# ECG_AFE_ADS1292.net
KiCad netlist of a schematic drawn in Altium Designer
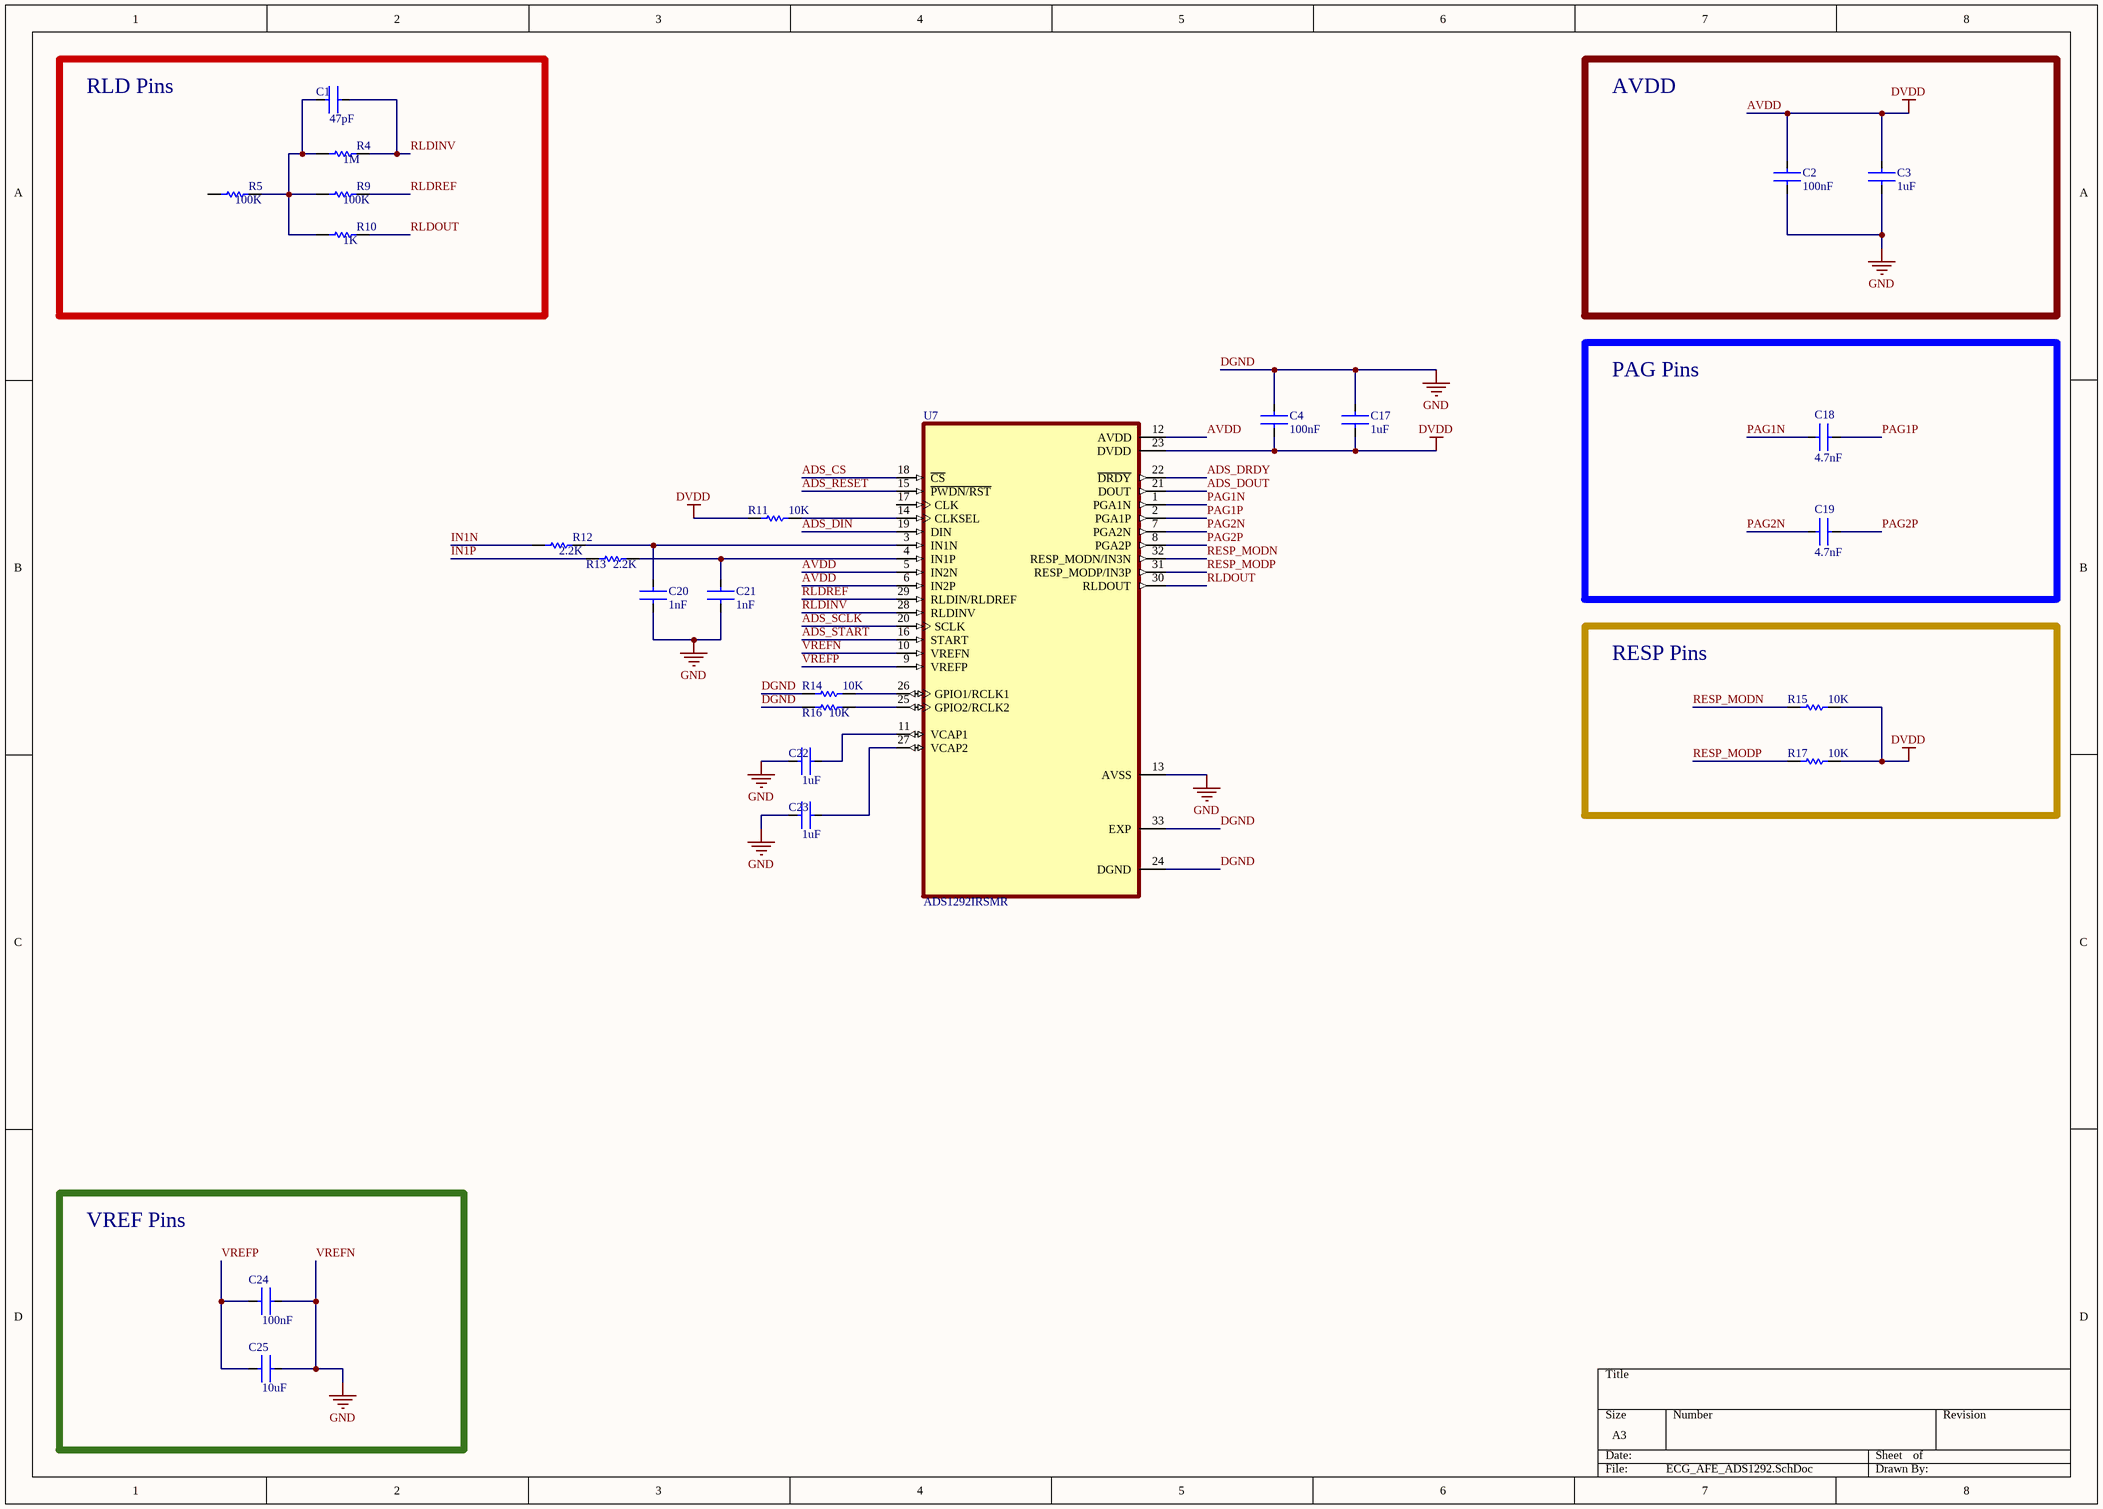
[diagram p0: ECG_AFE_ADS1292.SchDoc]

(export (version "E")
  (design (tool "Eeschema 10.0.6"))
  (components
    (comp (ref "C1")
      (value "47pF")
      (footprint "C_0805")
      (libsource (lib "ecg_device_components") (part "CAP-0805-16V-SMD-IPC_A"))
    )
    (comp (ref "C2")
      (value "100nF")
      (footprint "C_0805")
      (libsource (lib "ecg_device_components") (part "CAP-0805-16V-SMD-IPC_A"))
    )
    (comp (ref "C3")
      (value "1uF")
      (footprint "C_0805")
      (libsource (lib "ecg_device_components") (part "CAP-0805-16V-SMD-IPC_A"))
    )
    (comp (ref "C4")
      (value "100nF")
      (footprint "C_0805")
      (libsource (lib "ecg_device_components") (part "CAP-0805-16V-SMD-IPC_A"))
    )
    (comp (ref "C17")
      (value "1uF")
      (footprint "C_0805")
      (libsource (lib "ecg_device_components") (part "CAP-0805-16V-SMD-IPC_A"))
    )
    (comp (ref "C18")
      (value "4.7nF")
      (footprint "C_0805")
      (libsource (lib "ecg_device_components") (part "CAP-0805-16V-SMD-IPC_A"))
    )
    (comp (ref "C19")
      (value "4.7nF")
      (footprint "C_0805")
      (libsource (lib "ecg_device_components") (part "CAP-0805-16V-SMD-IPC_A"))
    )
    (comp (ref "C20")
      (value "1nF")
      (footprint "C_0805")
      (libsource (lib "ecg_device_components") (part "CAP-0805-16V-SMD-IPC_A"))
    )
    (comp (ref "C21")
      (value "1nF")
      (footprint "C_0805")
      (libsource (lib "ecg_device_components") (part "CAP-0805-16V-SMD-IPC_A"))
    )
    (comp (ref "C22")
      (value "1uF")
      (footprint "C_0805")
      (libsource (lib "ecg_device_components") (part "CAP-0805-16V-SMD-IPC_A"))
    )
    (comp (ref "C23")
      (value "1uF")
      (footprint "C_0805")
      (libsource (lib "ecg_device_components") (part "CAP-0805-16V-SMD-IPC_A"))
    )
    (comp (ref "C24")
      (value "100nF")
      (footprint "C_0805")
      (libsource (lib "ecg_device_components") (part "CAP-0805-16V-SMD-IPC_A"))
    )
    (comp (ref "C25")
      (value "10uF")
      (footprint "C_0805")
      (libsource (lib "ecg_device_components") (part "CAP-0805-16V-SMD-IPC_A"))
    )
    (comp (ref "R4")
      (value "1M")
      (footprint "RESC2013X60X35ML10T20")
      (libsource (lib "ecg_device_components") (part "10k 0805"))
    )
    (comp (ref "R5")
      (value "100K")
      (footprint "RESC2013X60X35ML10T20")
      (libsource (lib "ecg_device_components") (part "10k 0805"))
    )
    (comp (ref "R9")
      (value "100K")
      (footprint "RESC2013X60X35ML10T20")
      (libsource (lib "ecg_device_components") (part "10k 0805"))
    )
    (comp (ref "R10")
      (value "1K")
      (footprint "RESC2013X60X35ML10T20")
      (libsource (lib "ecg_device_components") (part "10k 0805"))
    )
    (comp (ref "R11")
      (value "10K")
      (footprint "RESC2013X60X35ML10T20")
      (libsource (lib "ecg_device_components") (part "10k 0805"))
    )
    (comp (ref "R12")
      (value "2.2K")
      (footprint "RESC2013X60X35ML10T20")
      (libsource (lib "ecg_device_components") (part "10k 0805"))
    )
    (comp (ref "R13")
      (value "2.2K")
      (footprint "RESC2013X60X35ML10T20")
      (libsource (lib "ecg_device_components") (part "10k 0805"))
    )
    (comp (ref "R14")
      (value "10K")
      (footprint "RESC2013X60X35ML10T20")
      (libsource (lib "ecg_device_components") (part "10k 0805"))
    )
    (comp (ref "R15")
      (value "10K")
      (footprint "RESC2013X60X35ML10T20")
      (libsource (lib "ecg_device_components") (part "10k 0805"))
    )
    (comp (ref "R16")
      (value "10K")
      (footprint "RESC2013X60X35ML10T20")
      (libsource (lib "ecg_device_components") (part "10k 0805"))
    )
    (comp (ref "R17")
      (value "10K")
      (footprint "RESC2013X60X35ML10T20")
      (libsource (lib "ecg_device_components") (part "10k 0805"))
    )
    (comp (ref "U7")
      (value "ADS1292IRSMR")
      (footprint "QFN40P400X400X100-33N")
      (description "24-bit, 2-ch, Low-Power Analog Front END (AFE) for ECG Applications")
      (fields (field (name "MF") "Texas Instruments"))
      (libsource (lib "ecg_device_components") (part "ADS1292IRSMR"))
    )
  )
  (nets
    (net (code "1") (name "/ADS_CS") (class "Default")
      (node (ref "U7") (pin "18") (pinfunction "~{CS}_18") (pintype "input"))
    )
    (net (code "2") (name "/ADS_DIN") (class "Default")
      (node (ref "U7") (pin "19") (pinfunction "DIN_19") (pintype "input"))
    )
    (net (code "3") (name "/ADS_DOUT") (class "Default")
      (node (ref "U7") (pin "21") (pinfunction "DOUT_21") (pintype "output"))
    )
    (net (code "4") (name "/ADS_DRDY") (class "Default")
      (node (ref "U7") (pin "22") (pinfunction "~{DRDY}_22") (pintype "output"))
    )
    (net (code "5") (name "/ADS_RESET") (class "Default")
      (node (ref "U7") (pin "15") (pinfunction "~{PWDN/RST}_15") (pintype "input"))
    )
    (net (code "6") (name "/ADS_SCLK") (class "Default")
      (node (ref "U7") (pin "20") (pinfunction "SCLK_20") (pintype "input"))
    )
    (net (code "7") (name "/ADS_START") (class "Default")
      (node (ref "U7") (pin "16") (pinfunction "START_16") (pintype "input"))
    )
    (net (code "8") (name "/IN1N") (class "Default")
      (node (ref "R12") (pin "1") (pinfunction "1_1") (pintype "passive"))
    )
    (net (code "9") (name "/IN1P") (class "Default")
      (node (ref "R13") (pin "1") (pinfunction "1_1") (pintype "passive"))
    )
    (net (code "10") (name "/PAG1N") (class "Default")
      (node (ref "C18") (pin "2") (pinfunction "2_2") (pintype "passive"))
      (node (ref "U7") (pin "1") (pinfunction "PGA1N_1") (pintype "output"))
    )
    (net (code "11") (name "/PAG1P") (class "Default")
      (node (ref "C18") (pin "1") (pinfunction "1_1") (pintype "passive"))
      (node (ref "U7") (pin "2") (pinfunction "PGA1P_2") (pintype "output"))
    )
    (net (code "12") (name "/PAG2N") (class "Default")
      (node (ref "C19") (pin "2") (pinfunction "2_2") (pintype "passive"))
      (node (ref "U7") (pin "7") (pinfunction "PGA2N_7") (pintype "output"))
    )
    (net (code "13") (name "/PAG2P") (class "Default")
      (node (ref "C19") (pin "1") (pinfunction "1_1") (pintype "passive"))
      (node (ref "U7") (pin "8") (pinfunction "PGA2P_8") (pintype "output"))
    )
    (net (code "14") (name "/RESP_MODN") (class "Default")
      (node (ref "R15") (pin "1") (pinfunction "1_1") (pintype "passive"))
      (node (ref "U7") (pin "32") (pinfunction "RESP_MODN/IN3N_32") (pintype "output"))
    )
    (net (code "15") (name "/RESP_MODP") (class "Default")
      (node (ref "R17") (pin "1") (pinfunction "1_1") (pintype "passive"))
      (node (ref "U7") (pin "31") (pinfunction "RESP_MODP/IN3P_31") (pintype "output"))
    )
    (net (code "16") (name "/RLDINV") (class "Default")
      (node (ref "C1") (pin "2") (pinfunction "2_2") (pintype "passive"))
      (node (ref "R4") (pin "2") (pinfunction "2_2") (pintype "passive"))
      (node (ref "U7") (pin "28") (pinfunction "RLDINV_28") (pintype "input"))
    )
    (net (code "17") (name "/RLDOUT") (class "Default")
      (node (ref "R10") (pin "2") (pinfunction "2_2") (pintype "passive"))
      (node (ref "U7") (pin "30") (pinfunction "RLDOUT_30") (pintype "output"))
    )
    (net (code "18") (name "/RLDREF") (class "Default")
      (node (ref "R9") (pin "2") (pinfunction "2_2") (pintype "passive"))
      (node (ref "U7") (pin "29") (pinfunction "RLDIN/RLDREF_29") (pintype "input"))
    )
    (net (code "19") (name "/VREFP") (class "Default")
      (node (ref "C24") (pin "1") (pinfunction "1_1") (pintype "passive"))
      (node (ref "C25") (pin "1") (pinfunction "1_1") (pintype "passive"))
      (node (ref "U7") (pin "9") (pinfunction "VREFP_9") (pintype "input"))
    )
    (net (code "20") (name "DVDD") (class "Default")
      (node (ref "C17") (pin "1") (pinfunction "1_1") (pintype "passive"))
      (node (ref "C2") (pin "2") (pinfunction "2_2") (pintype "passive"))
      (node (ref "C3") (pin "2") (pinfunction "2_2") (pintype "passive"))
      (node (ref "C4") (pin "1") (pinfunction "1_1") (pintype "passive"))
      (node (ref "R11") (pin "1") (pinfunction "1_1") (pintype "passive"))
      (node (ref "R15") (pin "2") (pinfunction "2_2") (pintype "passive"))
      (node (ref "R17") (pin "2") (pinfunction "2_2") (pintype "passive"))
      (node (ref "U7") (pin "12") (pinfunction "AVDD_12") (pintype "power_in"))
      (node (ref "U7") (pin "23") (pinfunction "DVDD_23") (pintype "power_in"))
      (node (ref "U7") (pin "5") (pinfunction "IN2N_5") (pintype "input"))
      (node (ref "U7") (pin "6") (pinfunction "IN2P_6") (pintype "input"))
    )
    (net (code "21") (name "GND") (class "Default")
      (node (ref "C17") (pin "2") (pinfunction "2_2") (pintype "passive"))
      (node (ref "C2") (pin "1") (pinfunction "1_1") (pintype "passive"))
      (node (ref "C20") (pin "1") (pinfunction "1_1") (pintype "passive"))
      (node (ref "C21") (pin "1") (pinfunction "1_1") (pintype "passive"))
      (node (ref "C22") (pin "1") (pinfunction "1_1") (pintype "passive"))
      (node (ref "C23") (pin "1") (pinfunction "1_1") (pintype "passive"))
      (node (ref "C24") (pin "2") (pinfunction "2_2") (pintype "passive"))
      (node (ref "C25") (pin "2") (pinfunction "2_2") (pintype "passive"))
      (node (ref "C3") (pin "1") (pinfunction "1_1") (pintype "passive"))
      (node (ref "C4") (pin "2") (pinfunction "2_2") (pintype "passive"))
      (node (ref "R14") (pin "1") (pinfunction "1_1") (pintype "passive"))
      (node (ref "R16") (pin "1") (pinfunction "1_1") (pintype "passive"))
      (node (ref "U7") (pin "10") (pinfunction "VREFN_10") (pintype "input"))
      (node (ref "U7") (pin "13") (pinfunction "AVSS_13") (pintype "power_in"))
      (node (ref "U7") (pin "24") (pinfunction "DGND_24") (pintype "power_in"))
      (node (ref "U7") (pin "33") (pinfunction "EXP_33") (pintype "power_in"))
    )
    (net (code "22") (name "Net-(C1-Pad1)") (class "Default")
      (node (ref "C1") (pin "1") (pinfunction "1_1") (pintype "passive"))
      (node (ref "R10") (pin "1") (pinfunction "1_1") (pintype "passive"))
      (node (ref "R4") (pin "1") (pinfunction "1_1") (pintype "passive"))
      (node (ref "R5") (pin "2") (pinfunction "2_2") (pintype "passive"))
      (node (ref "R9") (pin "1") (pinfunction "1_1") (pintype "passive"))
    )
    (net (code "23") (name "Net-(U7-CLKSEL)") (class "Default")
      (node (ref "R11") (pin "2") (pinfunction "2_2") (pintype "passive"))
      (node (ref "U7") (pin "14") (pinfunction "CLKSEL_14") (pintype "input"))
    )
    (net (code "24") (name "Net-(U7-GPIO1{slash}RCLK1)") (class "Default")
      (node (ref "R14") (pin "2") (pinfunction "2_2") (pintype "passive"))
      (node (ref "U7") (pin "26") (pinfunction "GPIO1/RCLK1_26") (pintype "bidirectional"))
    )
    (net (code "25") (name "Net-(U7-GPIO2{slash}RCLK2)") (class "Default")
      (node (ref "R16") (pin "2") (pinfunction "2_2") (pintype "passive"))
      (node (ref "U7") (pin "25") (pinfunction "GPIO2/RCLK2_25") (pintype "bidirectional"))
    )
    (net (code "26") (name "Net-(U7-IN1N)") (class "Default")
      (node (ref "C20") (pin "2") (pinfunction "2_2") (pintype "passive"))
      (node (ref "R12") (pin "2") (pinfunction "2_2") (pintype "passive"))
      (node (ref "U7") (pin "3") (pinfunction "IN1N_3") (pintype "input"))
    )
    (net (code "27") (name "Net-(U7-IN1P)") (class "Default")
      (node (ref "C21") (pin "2") (pinfunction "2_2") (pintype "passive"))
      (node (ref "R13") (pin "2") (pinfunction "2_2") (pintype "passive"))
      (node (ref "U7") (pin "4") (pinfunction "IN1P_4") (pintype "input"))
    )
    (net (code "28") (name "Net-(U7-VCAP1)") (class "Default")
      (node (ref "C22") (pin "2") (pinfunction "2_2") (pintype "passive"))
      (node (ref "U7") (pin "11") (pinfunction "VCAP1_11") (pintype "bidirectional"))
    )
    (net (code "29") (name "Net-(U7-VCAP2)") (class "Default")
      (node (ref "C23") (pin "2") (pinfunction "2_2") (pintype "passive"))
      (node (ref "U7") (pin "27") (pinfunction "VCAP2_27") (pintype "bidirectional"))
    )
    (net (code "30") (name "unconnected-(R5-Pad1)") (class "Default")
      (node (ref "R5") (pin "1") (pinfunction "1_1") (pintype "passive"))
    )
    (net (code "31") (name "unconnected-(U7-CLK-Pad17)") (class "Default")
      (node (ref "U7") (pin "17") (pinfunction "CLK_17") (pintype "input"))
    )
  )
)
